# 6_Power.net
KiCad netlist of a schematic drawn in Altium Designer
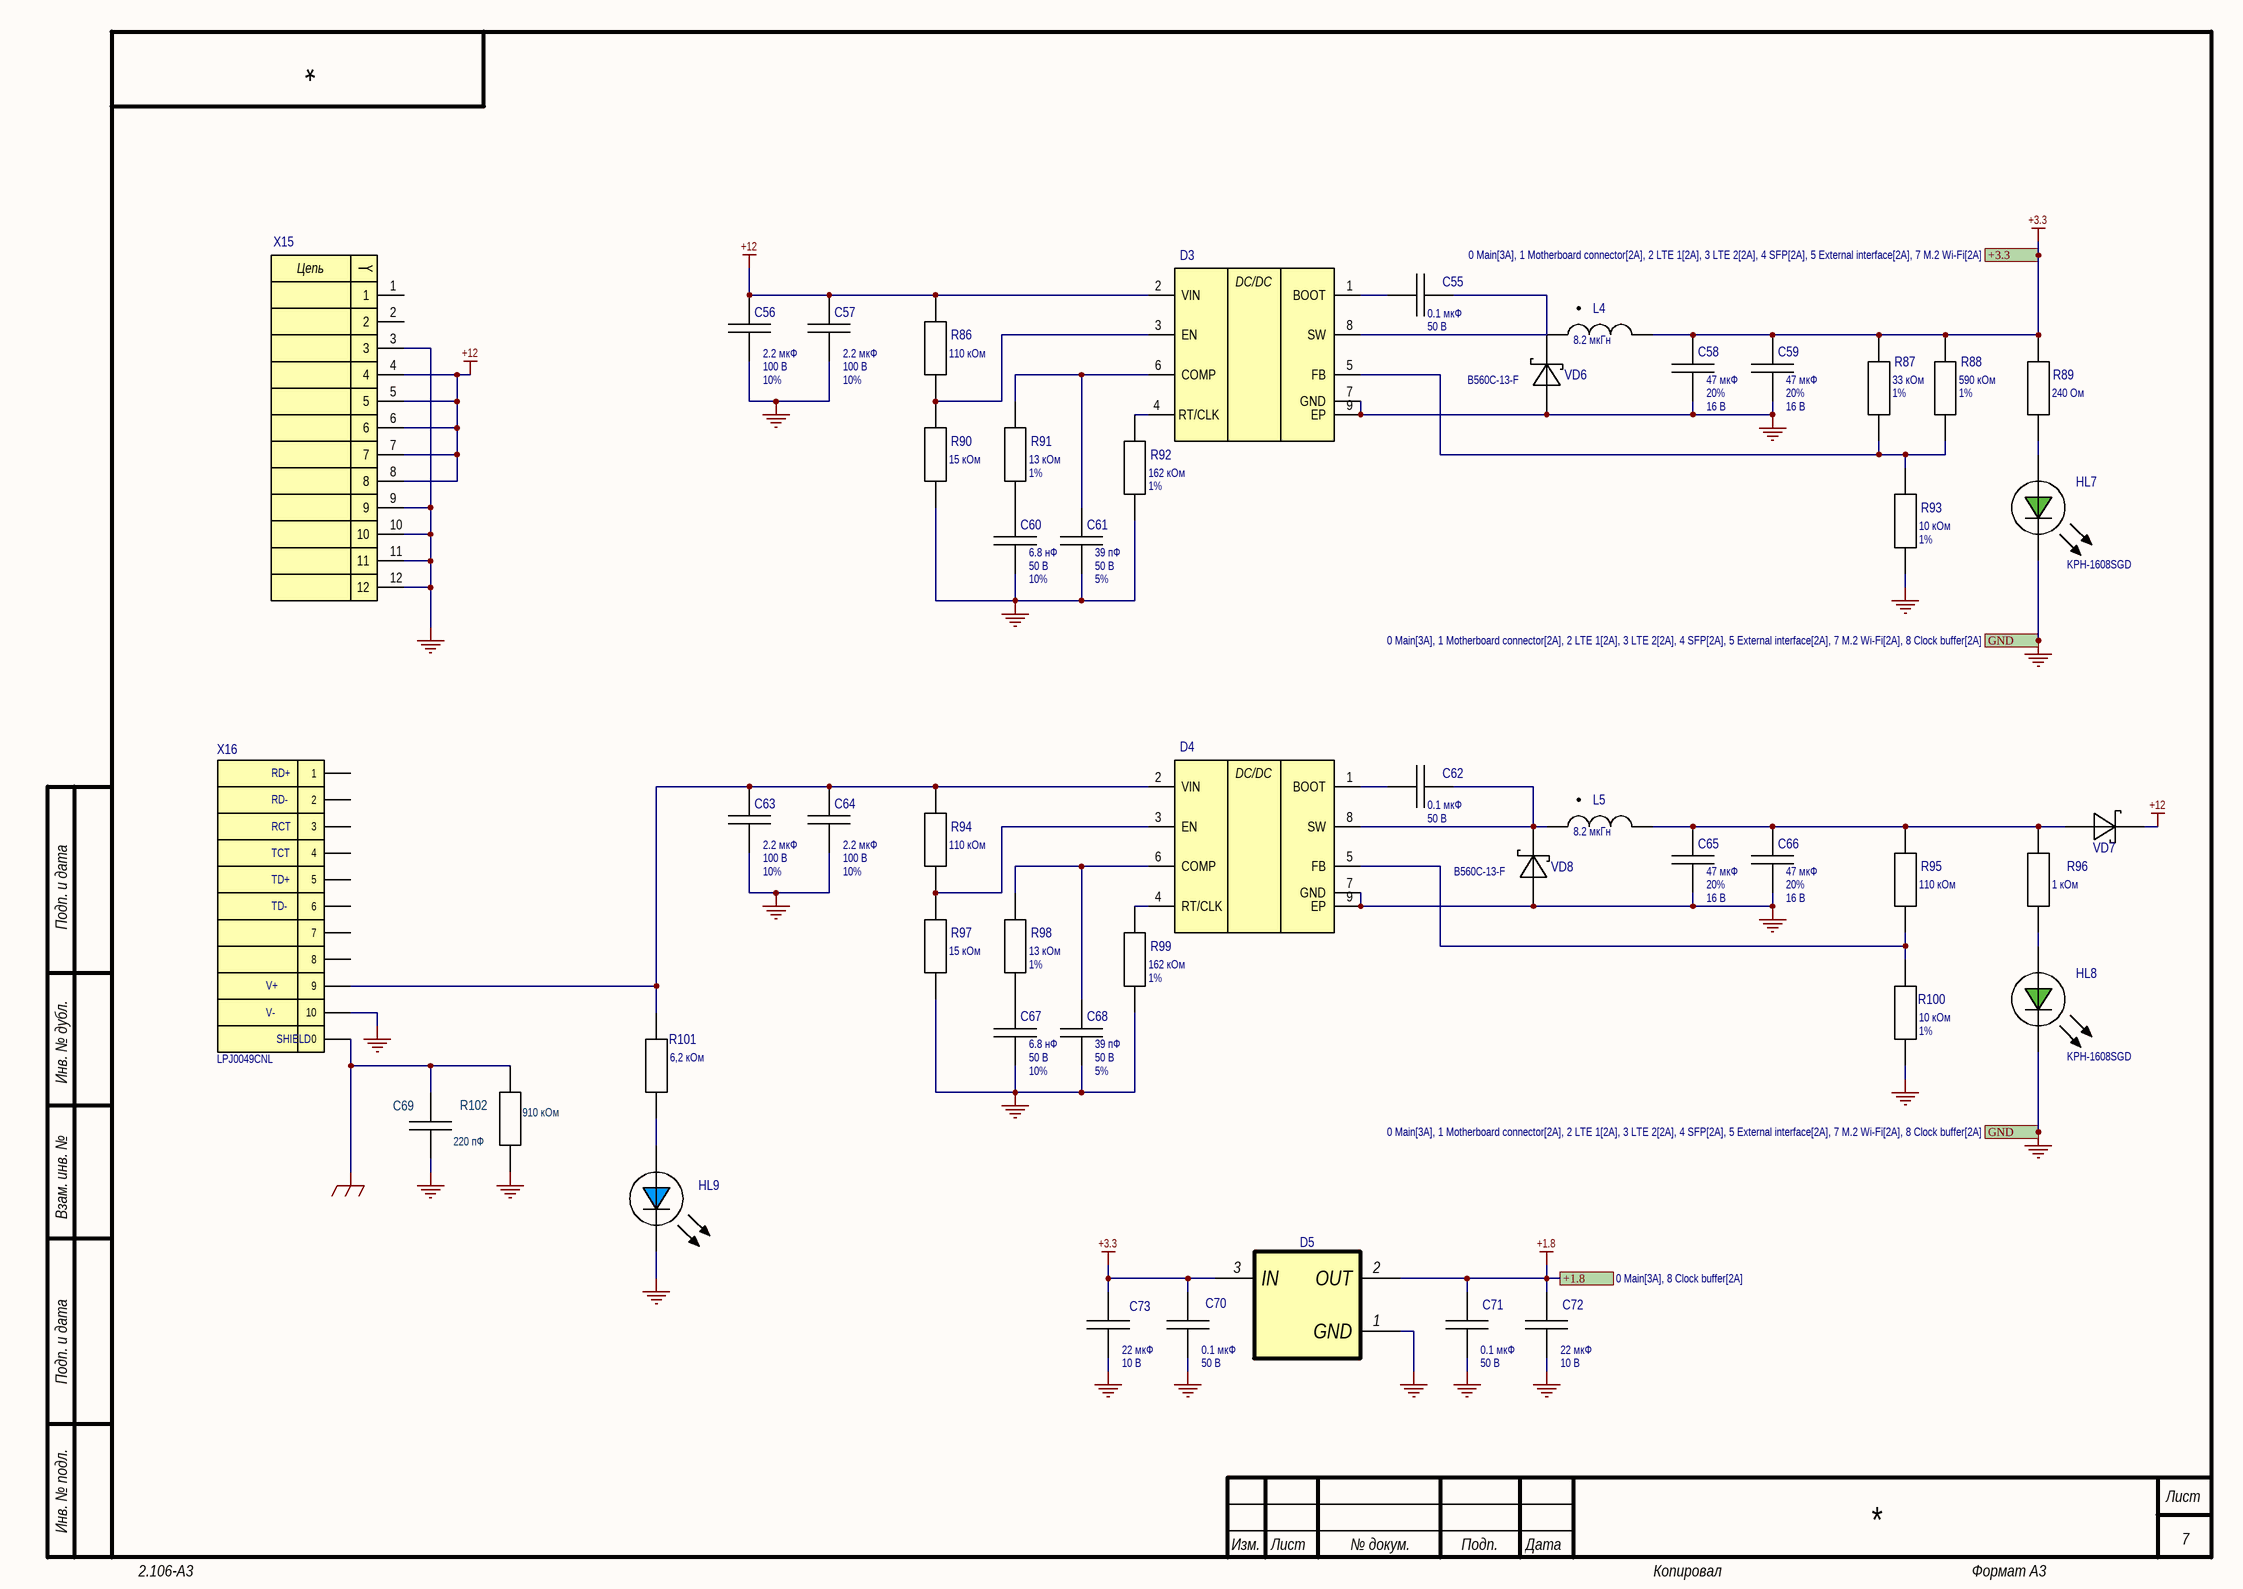
[diagram p0: 6 Power.SchDoc]

(export (version "E")
  (design (tool "Eeschema 10.0.6"))
  (components
    (comp (ref "C55")
      (value "0.1 мкФ")
      (footprint "CAP_0402")
      (description "Конденсатор CHIP-0402 0.1 мкФ 50 В 10% X7R")
      (fields
        (field (name "PARTNUMBER") "CC0402KRX7R9BB104")
        (field (name "TOLERANCE") "10%")
        (field (name "НАПРЯЖЕНИЕ") "50 В")
        (field (name "AUTOR") "Admin")
      )
      (libsource (lib "Database_Altium") (part "STD_CAP"))
    )
    (comp (ref "C56")
      (value "2.2 мкФ")
      (footprint "CAP_1206")
      (description "Конденсатор CHIP-1206 2.2 мкФ 100 В 10% X7R")
      (fields
        (field (name "PARTNUMBER") "GRM31CR72A225KA73L")
        (field (name "TOLERANCE") "10%")
        (field (name "НАПРЯЖЕНИЕ") "100 В")
        (field (name "MANUFACTURER") "MURATA")
        (field (name "AUTOR") "Admin")
      )
      (libsource (lib "Database_Altium") (part "STD_CAP"))
    )
    (comp (ref "C57")
      (value "2.2 мкФ")
      (footprint "CAP_1206")
      (description "Конденсатор CHIP-1206 2.2 мкФ 100 В 10% X7R")
      (fields
        (field (name "PARTNUMBER") "GRM31CR72A225KA73L")
        (field (name "TOLERANCE") "10%")
        (field (name "НАПРЯЖЕНИЕ") "100 В")
        (field (name "MANUFACTURER") "MURATA")
        (field (name "AUTOR") "Admin")
      )
      (libsource (lib "Database_Altium") (part "STD_CAP"))
    )
    (comp (ref "C58")
      (value "47 мкФ")
      (footprint "CAP_1210")
      (description "Конденсатор CHIP-1210 47 мкФ 16 В 20% X5R")
      (fields
        (field (name "PARTNUMBER") "GRM32ER61C476ME15L")
        (field (name "TOLERANCE") "20%")
        (field (name "НАПРЯЖЕНИЕ") "16 В")
        (field (name "MANUFACTURER") "MURATA")
        (field (name "AUTOR") "Цислав А.Н.")
      )
      (libsource (lib "Database_Altium") (part "STD_CAP"))
    )
    (comp (ref "C59")
      (value "47 мкФ")
      (footprint "CAP_1210")
      (description "Конденсатор CHIP-1210 47 мкФ 16 В 20% X5R")
      (fields
        (field (name "PARTNUMBER") "GRM32ER61C476ME15L")
        (field (name "TOLERANCE") "20%")
        (field (name "НАПРЯЖЕНИЕ") "16 В")
        (field (name "MANUFACTURER") "MURATA")
        (field (name "AUTOR") "Цислав А.Н.")
      )
      (libsource (lib "Database_Altium") (part "STD_CAP"))
    )
    (comp (ref "C60")
      (value "6.8 нФ")
      (footprint "CAP_0402")
      (description "Конденсатор CHIP-0402 6.8 нФ 50 В 10% X7R")
      (fields
        (field (name "PARTNUMBER") "CC0402KRX7R8BB682")
        (field (name "TOLERANCE") "10%")
        (field (name "НАПРЯЖЕНИЕ") "50 В")
        (field (name "MANUFACTURER") "YAGEO")
        (field (name "AUTOR") "Admin")
      )
      (libsource (lib "Database_Altium") (part "STD_CAP"))
    )
    (comp (ref "C61")
      (value "39 пФ")
      (footprint "CAP_0402")
      (description "Конденсатор CHIP-0402 39 пФ 50 В 5% NPO")
      (fields
        (field (name "PARTNUMBER") "CC0402JRNPO9BN390")
        (field (name "TOLERANCE") "5%")
        (field (name "НАПРЯЖЕНИЕ") "50 В")
        (field (name "MANUFACTURER") "YAGEO")
        (field (name "AUTOR") "Admin")
      )
      (libsource (lib "Database_Altium") (part "STD_CAP"))
    )
    (comp (ref "C62")
      (value "0.1 мкФ")
      (footprint "CAP_0402")
      (description "Конденсатор CHIP-0402 0.1 мкФ 50 В 10% X7R")
      (fields
        (field (name "PARTNUMBER") "CC0402KRX7R9BB104")
        (field (name "TOLERANCE") "10%")
        (field (name "НАПРЯЖЕНИЕ") "50 В")
        (field (name "AUTOR") "Admin")
      )
      (libsource (lib "Database_Altium") (part "STD_CAP"))
    )
    (comp (ref "C63")
      (value "2.2 мкФ")
      (footprint "CAP_1206")
      (description "Конденсатор CHIP-1206 2.2 мкФ 100 В 10% X7R")
      (fields
        (field (name "PARTNUMBER") "GRM31CR72A225KA73L")
        (field (name "TOLERANCE") "10%")
        (field (name "НАПРЯЖЕНИЕ") "100 В")
        (field (name "MANUFACTURER") "MURATA")
        (field (name "AUTOR") "Admin")
      )
      (libsource (lib "Database_Altium") (part "STD_CAP"))
    )
    (comp (ref "C64")
      (value "2.2 мкФ")
      (footprint "CAP_1206")
      (description "Конденсатор CHIP-1206 2.2 мкФ 100 В 10% X7R")
      (fields
        (field (name "PARTNUMBER") "GRM31CR72A225KA73L")
        (field (name "TOLERANCE") "10%")
        (field (name "НАПРЯЖЕНИЕ") "100 В")
        (field (name "MANUFACTURER") "MURATA")
        (field (name "AUTOR") "Admin")
      )
      (libsource (lib "Database_Altium") (part "STD_CAP"))
    )
    (comp (ref "C65")
      (value "47 мкФ")
      (footprint "CAP_1210")
      (description "Конденсатор CHIP-1210 47 мкФ 16 В 20% X5R")
      (fields
        (field (name "PARTNUMBER") "GRM32ER61C476ME15L")
        (field (name "TOLERANCE") "20%")
        (field (name "НАПРЯЖЕНИЕ") "16 В")
        (field (name "MANUFACTURER") "MURATA")
        (field (name "AUTOR") "Цислав А.Н.")
      )
      (libsource (lib "Database_Altium") (part "STD_CAP"))
    )
    (comp (ref "C66")
      (value "47 мкФ")
      (footprint "CAP_1210")
      (description "Конденсатор CHIP-1210 47 мкФ 16 В 20% X5R")
      (fields
        (field (name "PARTNUMBER") "GRM32ER61C476ME15L")
        (field (name "TOLERANCE") "20%")
        (field (name "НАПРЯЖЕНИЕ") "16 В")
        (field (name "MANUFACTURER") "MURATA")
        (field (name "AUTOR") "Цислав А.Н.")
      )
      (libsource (lib "Database_Altium") (part "STD_CAP"))
    )
    (comp (ref "C67")
      (value "6.8 нФ")
      (footprint "CAP_0402")
      (description "Конденсатор CHIP-0402 6.8 нФ 50 В 10% X7R")
      (fields
        (field (name "PARTNUMBER") "CC0402KRX7R8BB682")
        (field (name "TOLERANCE") "10%")
        (field (name "НАПРЯЖЕНИЕ") "50 В")
        (field (name "MANUFACTURER") "YAGEO")
        (field (name "AUTOR") "Admin")
      )
      (libsource (lib "Database_Altium") (part "STD_CAP"))
    )
    (comp (ref "C68")
      (value "39 пФ")
      (footprint "CAP_0402")
      (description "Конденсатор CHIP-0402 39 пФ 50 В 5% NPO")
      (fields
        (field (name "PARTNUMBER") "CC0402JRNPO9BN390")
        (field (name "TOLERANCE") "5%")
        (field (name "НАПРЯЖЕНИЕ") "50 В")
        (field (name "MANUFACTURER") "YAGEO")
        (field (name "AUTOR") "Admin")
      )
      (libsource (lib "Database_Altium") (part "STD_CAP"))
    )
    (comp (ref "C69")
      (value "220 пФ")
      (footprint "CAP_1812")
      (description "Конденсатор CHIP-1812 220 пФ 3000 В 5% NPO")
      (fields
        (field (name "PARTNUMBER") "CC1812JKNPOEBN221")
        (field (name "TOLERANCE") "5%")
        (field (name "AUTOR") "Admin")
      )
      (libsource (lib "Database_Altium") (part "STD_CAP"))
    )
    (comp (ref "C70")
      (value "0.1 мкФ")
      (footprint "CAP_0402")
      (description "Конденсатор CHIP-0402 0.1 мкФ 50 В 10% X7R")
      (fields
        (field (name "PARTNUMBER") "CC0402KRX7R9BB104")
        (field (name "TOLERANCE") "10%")
        (field (name "НАПРЯЖЕНИЕ") "50 В")
        (field (name "AUTOR") "Admin")
      )
      (libsource (lib "Database_Altium") (part "STD_CAP"))
    )
    (comp (ref "C71")
      (value "0.1 мкФ")
      (footprint "CAP_0402")
      (description "Конденсатор CHIP-0402 0.1 мкФ 50 В 10% X7R")
      (fields
        (field (name "PARTNUMBER") "CC0402KRX7R9BB104")
        (field (name "TOLERANCE") "10%")
        (field (name "НАПРЯЖЕНИЕ") "50 В")
        (field (name "AUTOR") "Admin")
      )
      (libsource (lib "Database_Altium") (part "STD_CAP"))
    )
    (comp (ref "C72")
      (value "22 мкФ")
      (footprint "CAP_0603")
      (description "Конденсатор CHIP-0603 22 мкФ 10 В 20% X5R")
      (fields
        (field (name "PARTNUMBER") "GRM188R61A226ME15")
        (field (name "TOLERANCE") "20%")
        (field (name "НАПРЯЖЕНИЕ") "10 В")
        (field (name "AUTOR") "Admin")
      )
      (libsource (lib "Database_Altium") (part "STD_CAP"))
    )
    (comp (ref "C73")
      (value "22 мкФ")
      (footprint "CAP_0603")
      (description "Конденсатор CHIP-0603 22 мкФ 10 В 20% X5R")
      (fields
        (field (name "PARTNUMBER") "GRM188R61A226ME15")
        (field (name "TOLERANCE") "20%")
        (field (name "НАПРЯЖЕНИЕ") "10 В")
        (field (name "AUTOR") "Admin")
      )
      (libsource (lib "Database_Altium") (part "STD_CAP"))
    )
    (comp (ref "D3")
      (value "TPS54360DDA")
      (footprint "HSOIC-8_EP")
      (description "Микросхема Texas Instruments   4.5 V to 60 V Input, 3.5 A, Step Down DC-DC Converter with Eco-mode")
      (fields
        (field (name "VOLTAGE") "60В")
        (field (name "MANUFACTURER") "Texas Instruments")
        (field (name "AUTOR") "Admin")
      )
      (libsource (lib "Database_Altium") (part "TPS54360"))
    )
    (comp (ref "D4")
      (value "TPS54360DDA")
      (footprint "HSOIC-8_EP")
      (description "Микросхема Texas Instruments   4.5 V to 60 V Input, 3.5 A, Step Down DC-DC Converter with Eco-mode")
      (fields
        (field (name "VOLTAGE") "60В")
        (field (name "MANUFACTURER") "Texas Instruments")
        (field (name "AUTOR") "Admin")
      )
      (libsource (lib "Database_Altium") (part "TPS54360"))
    )
    (comp (ref "D5")
      (value "GM1117-1.8ST3R")
      (footprint "SOT-223")
      (description "Микросхема Gamma Electronica  1,0 A Low-Dropout LDO")
      (fields
        (field (name "VOLTAGE") "1,8 В")
        (field (name "MANUFACTURER") "Gamma Electronica")
        (field (name "AUTOR") "Admin")
      )
      (libsource (lib "Database_Altium") (part "1117"))
    )
    (comp (ref "HL7")
      (value "KPH-1608SGD")
      (footprint "LED_0603_GREEN")
      (description "Диод Kingbright 2 В 20 мА GREEN")
      (fields
        (field (name "PARTNUMBER") "KPH-1608SGD")
        (field (name "MANUFACTURER") "Kingbright")
        (field (name "AUTOR") "Admin")
      )
      (libsource (lib "Database_Altium") (part "KPH-1608SGD"))
    )
    (comp (ref "HL8")
      (value "KPH-1608SGD")
      (footprint "LED_0603_GREEN")
      (description "Диод Kingbright 2 В 20 мА GREEN")
      (fields
        (field (name "PARTNUMBER") "KPH-1608SGD")
        (field (name "MANUFACTURER") "Kingbright")
        (field (name "AUTOR") "Admin")
      )
      (libsource (lib "Database_Altium") (part "KPH-1608SGD"))
    )
    (comp (ref "HL9")
      (value "XL-1608UBC-04")
      (footprint "LED_0603_BLUE")
      (description "Диод XINGLIGHT 3,3 В 20 мА")
      (fields (field (name "MANUFACTURER") "XINGLIGHT") (field (name "AUTOR") "Admin"))
      (libsource (lib "Database_Altium") (part "STD_LED_BLUE"))
    )
    (comp (ref "L4")
      (value "8.2 мкГн")
      (footprint "MWSA0603S")
      (description "Катушка индуктивности MWSA0603S 8.2 мкГн 20%")
      (fields
        (field (name "PARTNUMBER") "WSA0603S-8R2MT")
        (field (name "TOLERANCE") "20%")
        (field (name "AUTOR") "Admin")
      )
      (libsource (lib "Database_Altium") (part "STD_IND"))
    )
    (comp (ref "L5")
      (value "8.2 мкГн")
      (footprint "MWSA0603S")
      (description "Катушка индуктивности MWSA0603S 8.2 мкГн 20%")
      (fields
        (field (name "PARTNUMBER") "WSA0603S-8R2MT")
        (field (name "TOLERANCE") "20%")
        (field (name "AUTOR") "Admin")
      )
      (libsource (lib "Database_Altium") (part "STD_IND"))
    )
    (comp (ref "R86")
      (value "110 кОм")
      (footprint "RES_0603")
      (description "Резистор CHIP-0603 110 кОм 1%")
      (fields
        (field (name "PARTNUMBER") "RC0603FR-07110K")
        (field (name "TOLERANCE") "1%")
        (field (name "AUTOR") "Цислав А.Н.")
      )
      (libsource (lib "Database_Altium") (part "STD_RES"))
    )
    (comp (ref "R87")
      (value "33 кОм")
      (footprint "RES_0402")
      (description "Резистор CHIP-0402 33 кОм 1%")
      (fields
        (field (name "PARTNUMBER") "RC0402FR-0733KL")
        (field (name "TOLERANCE") "1%")
        (field (name "MANUFACTURER") "YAGEO")
        (field (name "AUTOR") "Цислав А.Н.")
      )
      (libsource (lib "Database_Altium") (part "STD_RES"))
    )
    (comp (ref "R88")
      (value "590 кОм")
      (footprint "RES_0603")
      (description "Резистор CHIP-0603 590 кОм 1%")
      (fields
        (field (name "PARTNUMBER") "RC0603FR-07590K")
        (field (name "TOLERANCE") "1%")
        (field (name "MANUFACTURER") "YAGEO")
        (field (name "AUTOR") "Admin")
      )
      (libsource (lib "Database_Altium") (part "STD_RES"))
    )
    (comp (ref "R89")
      (value "240 Ом")
      (footprint "RES_0402")
      (description "Резистор CHIP-0402 240 Ом 1%")
      (fields
        (field (name "PARTNUMBER") "RC0402FR-07240RL")
        (field (name "TOLERANCE") "1%")
        (field (name "AUTOR") "Цислав А.Н.")
      )
      (libsource (lib "Database_Altium") (part "STD_RES"))
    )
    (comp (ref "R90")
      (value "15 кОм")
      (footprint "RES_0402")
      (description "Резистор CHIP-0402 15 кОм 1%")
      (fields
        (field (name "PARTNUMBER") "RC0402FR-0715KL")
        (field (name "TOLERANCE") "1%")
        (field (name "AUTOR") "Цислав А.Н.")
      )
      (libsource (lib "Database_Altium") (part "STD_RES"))
    )
    (comp (ref "R91")
      (value "13 кОм")
      (footprint "RES_0402")
      (description "Резистор CHIP-0402 13 кОм 1%")
      (fields
        (field (name "PARTNUMBER") "RC0402FR-0713KL")
        (field (name "TOLERANCE") "1%")
        (field (name "MANUFACTURER") "YAGEO")
        (field (name "AUTOR") "Цислав А.Н.")
      )
      (libsource (lib "Database_Altium") (part "STD_RES"))
    )
    (comp (ref "R92")
      (value "162 кОм")
      (footprint "RES_0603")
      (description "Резистор CHIP-0603 162 кОм 1%")
      (fields
        (field (name "PARTNUMBER") "RC0603FR-07162K")
        (field (name "TOLERANCE") "1%")
        (field (name "MANUFACTURER") "YAGEO")
        (field (name "AUTOR") "Цислав А.Н.")
      )
      (libsource (lib "Database_Altium") (part "STD_RES"))
    )
    (comp (ref "R93")
      (value "10 кОм")
      (footprint "RES_0402")
      (description "Резистор CHIP-0402 10 кОм 1%")
      (fields
        (field (name "PARTNUMBER") "RC0402FR-0710KL")
        (field (name "TOLERANCE") "1%")
        (field (name "MANUFACTURER") "YAGEO")
        (field (name "AUTOR") "Цислав А.Н.")
      )
      (libsource (lib "Database_Altium") (part "STD_RES"))
    )
    (comp (ref "R94")
      (value "110 кОм")
      (footprint "RES_0603")
      (description "Резистор CHIP-0603 110 кОм 1%")
      (fields
        (field (name "PARTNUMBER") "RC0603FR-07110K")
        (field (name "TOLERANCE") "1%")
        (field (name "AUTOR") "Цислав А.Н.")
      )
      (libsource (lib "Database_Altium") (part "STD_RES"))
    )
    (comp (ref "R95")
      (value "110 кОм")
      (footprint "RES_0603")
      (description "Резистор CHIP-0603 110 кОм 1%")
      (fields
        (field (name "PARTNUMBER") "RC0603FR-07110K")
        (field (name "TOLERANCE") "1%")
        (field (name "AUTOR") "Цислав А.Н.")
      )
      (libsource (lib "Database_Altium") (part "STD_RES"))
    )
    (comp (ref "R96")
      (value "1 кОм")
      (footprint "RES_0402")
      (description "Резистор CHIP-0402 1 кОм 5%")
      (fields
        (field (name "PARTNUMBER") "RC0402JR-071KL")
        (field (name "TOLERANCE") "5%")
        (field (name "AUTOR") "Цислав А.Н.")
      )
      (libsource (lib "Database_Altium") (part "STD_RES"))
    )
    (comp (ref "R97")
      (value "15 кОм")
      (footprint "RES_0402")
      (description "Резистор CHIP-0402 15 кОм 1%")
      (fields
        (field (name "PARTNUMBER") "RC0402FR-0715KL")
        (field (name "TOLERANCE") "1%")
        (field (name "AUTOR") "Цислав А.Н.")
      )
      (libsource (lib "Database_Altium") (part "STD_RES"))
    )
    (comp (ref "R98")
      (value "13 кОм")
      (footprint "RES_0402")
      (description "Резистор CHIP-0402 13 кОм 1%")
      (fields
        (field (name "PARTNUMBER") "RC0402FR-0713KL")
        (field (name "TOLERANCE") "1%")
        (field (name "MANUFACTURER") "YAGEO")
        (field (name "AUTOR") "Цислав А.Н.")
      )
      (libsource (lib "Database_Altium") (part "STD_RES"))
    )
    (comp (ref "R99")
      (value "162 кОм")
      (footprint "RES_0603")
      (description "Резистор CHIP-0603 162 кОм 1%")
      (fields
        (field (name "PARTNUMBER") "RC0603FR-07162K")
        (field (name "TOLERANCE") "1%")
        (field (name "MANUFACTURER") "YAGEO")
        (field (name "AUTOR") "Цислав А.Н.")
      )
      (libsource (lib "Database_Altium") (part "STD_RES"))
    )
    (comp (ref "R100")
      (value "10 кОм")
      (footprint "RES_0402")
      (description "Резистор CHIP-0402 10 кОм 1%")
      (fields
        (field (name "PARTNUMBER") "RC0402FR-0710KL")
        (field (name "TOLERANCE") "1%")
        (field (name "MANUFACTURER") "YAGEO")
        (field (name "AUTOR") "Цислав А.Н.")
      )
      (libsource (lib "Database_Altium") (part "STD_RES"))
    )
    (comp (ref "R101")
      (value "6,2 кОм")
      (footprint "RES_0805")
      (description "Резистор CHIP-0805 6,2 кОм 5%")
      (fields
        (field (name "PARTNUMBER") "RC0805JR-076K2L")
        (field (name "TOLERANCE") "5%")
        (field (name "AUTOR") "Admin")
      )
      (libsource (lib "Database_Altium") (part "STD_RES"))
    )
    (comp (ref "R102")
      (value "910 кОм")
      (footprint "RES_1206")
      (description "Резистор CHIP-1206 910 кОм 1%")
      (fields
        (field (name "PARTNUMBER") "RC1206FR-07910KL")
        (field (name "TOLERANCE") "1%")
        (field (name "AUTOR") "Admin")
      )
      (libsource (lib "Database_Altium") (part "STD_RES"))
    )
    (comp (ref "VD6")
      (value "STD_DIODE_SCHOTTKY")
      (footprint "SMC")
      (description "Диод Diodes 700 мВ 5 А")
      (fields
        (field (name "PARTNUMBER") "B560C-13-F")
        (field (name "MANUFACTURER") "Diodes")
        (field (name "AUTOR") "Admin")
      )
      (libsource (lib "Database_Altium") (part "STD_DIODE_SCHOTTKY"))
    )
    (comp (ref "VD7")
      (value "STD_DIODE_SCHOTTKY")
      (footprint "TO277A")
      (description "Диод Vishay 590 мВ 10 А")
      (fields
        (field (name "PARTNUMBER") "V10P20-M3")
        (field (name "MANUFACTURER") "Vishay")
        (field (name "AUTOR") "Цислав А.Н.")
      )
      (libsource (lib "Database_Altium") (part "STD_DIODE_SCHOTTKY"))
    )
    (comp (ref "VD8")
      (value "STD_DIODE_SCHOTTKY")
      (footprint "SMC")
      (description "Диод Diodes 700 мВ 5 А")
      (fields
        (field (name "PARTNUMBER") "B560C-13-F")
        (field (name "MANUFACTURER") "Diodes")
        (field (name "AUTOR") "Admin")
      )
      (libsource (lib "Database_Altium") (part "STD_DIODE_SCHOTTKY"))
    )
    (comp (ref "X15")
      (value "STD_CON12")
      (footprint "61301221121")
      (description "Разъем Wurth PLD")
      (fields
        (field (name "PARTNUMBER") "61301221121")
        (field (name "MANUFACTURER") "Wurth")
        (field (name "CONTACT") "12")
        (field (name "AUTOR") "Admin")
      )
      (libsource (lib "Database_Altium") (part "STD_CON12"))
    )
    (comp (ref "X16")
      (value "LPJ0049CNL")
      (footprint "LPJ0049CNL")
      (description "Разъем LINK-PP RJ-45")
      (fields
        (field (name "MANUFACTURER") "LINK-PP")
        (field (name "CONTACT") "10")
        (field (name "AUTOR") "Admin")
      )
      (libsource (lib "Database_Altium") (part "LPJ0049CNL"))
    )
  )
  (nets
    (net (code "1") (name "+1.8") (class "Default")
      (node (ref "C71") (pin "1") (pinfunction "1_1") (pintype "passive"))
      (node (ref "C72") (pin "1") (pinfunction "1_1") (pintype "passive"))
      (node (ref "D5") (pin "2") (pinfunction "OUT_2") (pintype "power_in"))
    )
    (net (code "2") (name "+3.3") (class "Default")
      (node (ref "C58") (pin "1") (pinfunction "1_1") (pintype "passive"))
      (node (ref "C59") (pin "1") (pinfunction "1_1") (pintype "passive"))
      (node (ref "C70") (pin "1") (pinfunction "1_1") (pintype "passive"))
      (node (ref "C73") (pin "1") (pinfunction "1_1") (pintype "passive"))
      (node (ref "D5") (pin "3") (pinfunction "IN_3") (pintype "power_in"))
      (node (ref "L4") (pin "2") (pinfunction "2_2") (pintype "passive"))
      (node (ref "R87") (pin "2") (pinfunction "2_2") (pintype "passive"))
      (node (ref "R88") (pin "2") (pinfunction "2_2") (pintype "passive"))
      (node (ref "R89") (pin "2") (pinfunction "2_2") (pintype "passive"))
    )
    (net (code "3") (name "+12") (class "Default")
      (node (ref "C56") (pin "1") (pinfunction "1_1") (pintype "passive"))
      (node (ref "C57") (pin "1") (pinfunction "1_1") (pintype "passive"))
      (node (ref "D3") (pin "2") (pinfunction "VIN_2") (pintype "passive"))
      (node (ref "R86") (pin "2") (pinfunction "2_2") (pintype "passive"))
      (node (ref "VD7") (pin "1") (pinfunction "1_1") (pintype "passive"))
      (node (ref "X15") (pin "4") (pinfunction "4_4") (pintype "passive"))
      (node (ref "X15") (pin "5") (pinfunction "5_5") (pintype "passive"))
      (node (ref "X15") (pin "6") (pinfunction "6_6") (pintype "passive"))
      (node (ref "X15") (pin "7") (pinfunction "7_7") (pintype "passive"))
      (node (ref "X15") (pin "8") (pinfunction "8_8") (pintype "passive"))
    )
    (net (code "4") (name "GND") (class "Default")
      (node (ref "C56") (pin "2") (pinfunction "2_2") (pintype "passive"))
      (node (ref "C57") (pin "2") (pinfunction "2_2") (pintype "passive"))
      (node (ref "C58") (pin "2") (pinfunction "2_2") (pintype "passive"))
      (node (ref "C59") (pin "2") (pinfunction "2_2") (pintype "passive"))
      (node (ref "C60") (pin "2") (pinfunction "2_2") (pintype "passive"))
      (node (ref "C61") (pin "2") (pinfunction "2_2") (pintype "passive"))
      (node (ref "C63") (pin "2") (pinfunction "2_2") (pintype "passive"))
      (node (ref "C64") (pin "2") (pinfunction "2_2") (pintype "passive"))
      (node (ref "C65") (pin "2") (pinfunction "2_2") (pintype "passive"))
      (node (ref "C66") (pin "2") (pinfunction "2_2") (pintype "passive"))
      (node (ref "C67") (pin "2") (pinfunction "2_2") (pintype "passive"))
      (node (ref "C68") (pin "2") (pinfunction "2_2") (pintype "passive"))
      (node (ref "C69") (pin "1") (pinfunction "1_1") (pintype "passive"))
      (node (ref "C70") (pin "2") (pinfunction "2_2") (pintype "passive"))
      (node (ref "C71") (pin "2") (pinfunction "2_2") (pintype "passive"))
      (node (ref "C72") (pin "2") (pinfunction "2_2") (pintype "passive"))
      (node (ref "C73") (pin "2") (pinfunction "2_2") (pintype "passive"))
      (node (ref "D3") (pin "7") (pinfunction "GND_7") (pintype "power_in"))
      (node (ref "D3") (pin "9") (pinfunction "EP_9") (pintype "power_in"))
      (node (ref "D4") (pin "7") (pinfunction "GND_7") (pintype "power_in"))
      (node (ref "D4") (pin "9") (pinfunction "EP_9") (pintype "power_in"))
      (node (ref "D5") (pin "1") (pinfunction "GND_1") (pintype "power_in"))
      (node (ref "HL7") (pin "2") (pinfunction "K_2") (pintype "power_in"))
      (node (ref "HL8") (pin "2") (pinfunction "K_2") (pintype "power_in"))
      (node (ref "HL9") (pin "2") (pinfunction "K_2") (pintype "power_in"))
      (node (ref "R100") (pin "1") (pinfunction "1_1") (pintype "passive"))
      (node (ref "R102") (pin "1") (pinfunction "1_1") (pintype "passive"))
      (node (ref "R90") (pin "1") (pinfunction "1_1") (pintype "passive"))
      (node (ref "R92") (pin "1") (pinfunction "1_1") (pintype "passive"))
      (node (ref "R93") (pin "1") (pinfunction "1_1") (pintype "passive"))
      (node (ref "R97") (pin "1") (pinfunction "1_1") (pintype "passive"))
      (node (ref "R99") (pin "1") (pinfunction "1_1") (pintype "passive"))
      (node (ref "VD6") (pin "2") (pinfunction "2_2") (pintype "passive"))
      (node (ref "VD8") (pin "2") (pinfunction "2_2") (pintype "passive"))
      (node (ref "X15") (pin "10") (pinfunction "10_10") (pintype "passive"))
      (node (ref "X15") (pin "11") (pinfunction "11_11") (pintype "passive"))
      (node (ref "X15") (pin "12") (pinfunction "12_12") (pintype "passive"))
      (node (ref "X15") (pin "3") (pinfunction "3_3") (pintype "passive"))
      (node (ref "X15") (pin "9") (pinfunction "9_9") (pintype "passive"))
      (node (ref "X16") (pin "10") (pinfunction "10_10") (pintype "passive"))
    )
    (net (code "5") (name "GNDG") (class "Default")
      (node (ref "C69") (pin "2") (pinfunction "2_2") (pintype "passive"))
      (node (ref "R102") (pin "2") (pinfunction "2_2") (pintype "passive"))
      (node (ref "X16") (pin "0") (pinfunction "0_0") (pintype "passive"))
    )
    (net (code "6") (name "Net-(C60-Pad1)") (class "Default")
      (node (ref "C60") (pin "1") (pinfunction "1_1") (pintype "passive"))
      (node (ref "R91") (pin "1") (pinfunction "1_1") (pintype "passive"))
    )
    (net (code "7") (name "Net-(C65-Pad1)") (class "Default")
      (node (ref "C65") (pin "1") (pinfunction "1_1") (pintype "passive"))
      (node (ref "C66") (pin "1") (pinfunction "1_1") (pintype "passive"))
      (node (ref "L5") (pin "2") (pinfunction "2_2") (pintype "passive"))
      (node (ref "R95") (pin "2") (pinfunction "2_2") (pintype "passive"))
      (node (ref "R96") (pin "2") (pinfunction "2_2") (pintype "passive"))
      (node (ref "VD7") (pin "2") (pinfunction "2_2") (pintype "passive"))
    )
    (net (code "8") (name "Net-(C67-Pad1)") (class "Default")
      (node (ref "C67") (pin "1") (pinfunction "1_1") (pintype "passive"))
      (node (ref "R98") (pin "1") (pinfunction "1_1") (pintype "passive"))
    )
    (net (code "9") (name "Net-(D3-BOOT)") (class "Default")
      (node (ref "C55") (pin "1") (pinfunction "1_1") (pintype "passive"))
      (node (ref "D3") (pin "1") (pinfunction "BOOT_1") (pintype "power_in"))
    )
    (net (code "10") (name "Net-(D3-COMP)") (class "Default")
      (node (ref "C61") (pin "1") (pinfunction "1_1") (pintype "passive"))
      (node (ref "D3") (pin "6") (pinfunction "COMP_6") (pintype "passive"))
      (node (ref "R91") (pin "2") (pinfunction "2_2") (pintype "passive"))
    )
    (net (code "11") (name "Net-(D3-EN)") (class "Default")
      (node (ref "D3") (pin "3") (pinfunction "EN_3") (pintype "passive"))
      (node (ref "R86") (pin "1") (pinfunction "1_1") (pintype "passive"))
      (node (ref "R90") (pin "2") (pinfunction "2_2") (pintype "passive"))
    )
    (net (code "12") (name "Net-(D3-FB)") (class "Default")
      (node (ref "D3") (pin "5") (pinfunction "FB_5") (pintype "power_in"))
      (node (ref "R87") (pin "1") (pinfunction "1_1") (pintype "passive"))
      (node (ref "R88") (pin "1") (pinfunction "1_1") (pintype "passive"))
      (node (ref "R93") (pin "2") (pinfunction "2_2") (pintype "passive"))
    )
    (net (code "13") (name "Net-(D3-RT{slash}CLK)") (class "Default")
      (node (ref "D3") (pin "4") (pinfunction "RT/CLK_4") (pintype "passive"))
      (node (ref "R92") (pin "2") (pinfunction "2_2") (pintype "passive"))
    )
    (net (code "14") (name "Net-(D3-SW)") (class "Default")
      (node (ref "C55") (pin "2") (pinfunction "2_2") (pintype "passive"))
      (node (ref "D3") (pin "8") (pinfunction "SW_8") (pintype "power_in"))
      (node (ref "L4") (pin "1") (pinfunction "1_1") (pintype "passive"))
      (node (ref "VD6") (pin "1") (pinfunction "1_1") (pintype "passive"))
    )
    (net (code "15") (name "Net-(D4-BOOT)") (class "Default")
      (node (ref "C62") (pin "1") (pinfunction "1_1") (pintype "passive"))
      (node (ref "D4") (pin "1") (pinfunction "BOOT_1") (pintype "power_in"))
    )
    (net (code "16") (name "Net-(D4-COMP)") (class "Default")
      (node (ref "C68") (pin "1") (pinfunction "1_1") (pintype "passive"))
      (node (ref "D4") (pin "6") (pinfunction "COMP_6") (pintype "passive"))
      (node (ref "R98") (pin "2") (pinfunction "2_2") (pintype "passive"))
    )
    (net (code "17") (name "Net-(D4-EN)") (class "Default")
      (node (ref "D4") (pin "3") (pinfunction "EN_3") (pintype "passive"))
      (node (ref "R94") (pin "1") (pinfunction "1_1") (pintype "passive"))
      (node (ref "R97") (pin "2") (pinfunction "2_2") (pintype "passive"))
    )
    (net (code "18") (name "Net-(D4-FB)") (class "Default")
      (node (ref "D4") (pin "5") (pinfunction "FB_5") (pintype "power_in"))
      (node (ref "R100") (pin "2") (pinfunction "2_2") (pintype "passive"))
      (node (ref "R95") (pin "1") (pinfunction "1_1") (pintype "passive"))
    )
    (net (code "19") (name "Net-(D4-RT{slash}CLK)") (class "Default")
      (node (ref "D4") (pin "4") (pinfunction "RT/CLK_4") (pintype "passive"))
      (node (ref "R99") (pin "2") (pinfunction "2_2") (pintype "passive"))
    )
    (net (code "20") (name "Net-(D4-SW)") (class "Default")
      (node (ref "C62") (pin "2") (pinfunction "2_2") (pintype "passive"))
      (node (ref "D4") (pin "8") (pinfunction "SW_8") (pintype "power_in"))
      (node (ref "L5") (pin "1") (pinfunction "1_1") (pintype "passive"))
      (node (ref "VD8") (pin "1") (pinfunction "1_1") (pintype "passive"))
    )
    (net (code "21") (name "Net-(D4-VIN)") (class "Default")
      (node (ref "C63") (pin "1") (pinfunction "1_1") (pintype "passive"))
      (node (ref "C64") (pin "1") (pinfunction "1_1") (pintype "passive"))
      (node (ref "D4") (pin "2") (pinfunction "VIN_2") (pintype "passive"))
      (node (ref "R101") (pin "2") (pinfunction "2_2") (pintype "passive"))
      (node (ref "R94") (pin "2") (pinfunction "2_2") (pintype "passive"))
      (node (ref "X16") (pin "9") (pinfunction "9_9") (pintype "passive"))
    )
    (net (code "22") (name "Net-(HL7-A)") (class "Default")
      (node (ref "HL7") (pin "1") (pinfunction "A_1") (pintype "power_in"))
      (node (ref "R89") (pin "1") (pinfunction "1_1") (pintype "passive"))
    )
    (net (code "23") (name "Net-(HL8-A)") (class "Default")
      (node (ref "HL8") (pin "1") (pinfunction "A_1") (pintype "power_in"))
      (node (ref "R96") (pin "1") (pinfunction "1_1") (pintype "passive"))
    )
    (net (code "24") (name "Net-(HL9-A)") (class "Default")
      (node (ref "HL9") (pin "1") (pinfunction "A_1") (pintype "power_in"))
      (node (ref "R101") (pin "1") (pinfunction "1_1") (pintype "passive"))
    )
    (net (code "25") (name "unconnected-(X15-Pad1)") (class "Default")
      (node (ref "X15") (pin "1") (pinfunction "1_1") (pintype "passive"))
    )
    (net (code "26") (name "unconnected-(X15-Pad2)") (class "Default")
      (node (ref "X15") (pin "2") (pinfunction "2_2") (pintype "passive"))
    )
    (net (code "27") (name "unconnected-(X16-Pad1)") (class "Default")
      (node (ref "X16") (pin "1") (pinfunction "1_1") (pintype "passive"))
    )
    (net (code "28") (name "unconnected-(X16-Pad2)") (class "Default")
      (node (ref "X16") (pin "2") (pinfunction "2_2") (pintype "passive"))
    )
    (net (code "29") (name "unconnected-(X16-Pad3)") (class "Default")
      (node (ref "X16") (pin "3") (pinfunction "3_3") (pintype "passive"))
    )
    (net (code "30") (name "unconnected-(X16-Pad4)") (class "Default")
      (node (ref "X16") (pin "4") (pinfunction "4_4") (pintype "passive"))
    )
    (net (code "31") (name "unconnected-(X16-Pad5)") (class "Default")
      (node (ref "X16") (pin "5") (pinfunction "5_5") (pintype "passive"))
    )
    (net (code "32") (name "unconnected-(X16-Pad6)") (class "Default")
      (node (ref "X16") (pin "6") (pinfunction "6_6") (pintype "passive"))
    )
    (net (code "33") (name "unconnected-(X16-Pad7)") (class "Default")
      (node (ref "X16") (pin "7") (pinfunction "7_7") (pintype "passive"))
    )
    (net (code "34") (name "unconnected-(X16-Pad8)") (class "Default")
      (node (ref "X16") (pin "8") (pinfunction "8_8") (pintype "passive"))
    )
  )
)
